# Filter_sim.net
KiCad netlist of a schematic drawn in Altium Designer
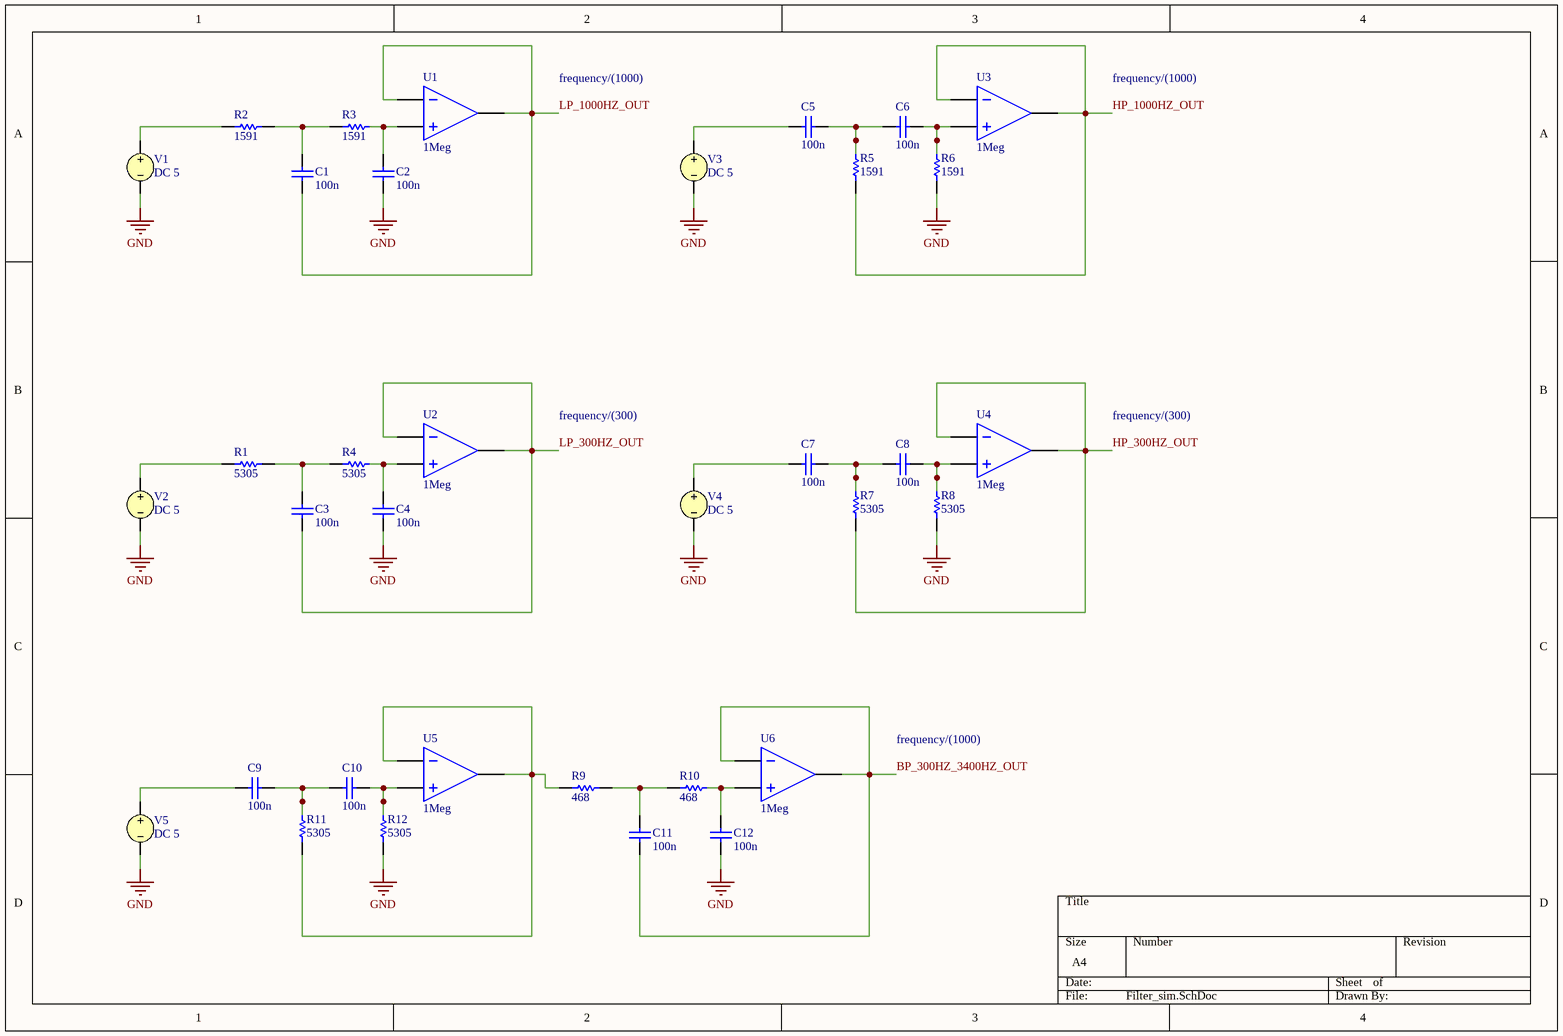
[diagram p0: Filter_sim.SchDoc]

(export (version "E")
  (design (tool "Eeschema 10.0.6"))
  (components
    (comp (ref "C1")
      (value "100n")
      (description "Capacitor")
      (libsource (lib "Simulation Generic Components") (part "Capacitor"))
    )
    (comp (ref "C2")
      (value "100n")
      (description "Capacitor")
      (libsource (lib "Simulation Generic Components") (part "Capacitor"))
    )
    (comp (ref "C3")
      (value "100n")
      (description "Capacitor")
      (libsource (lib "Simulation Generic Components") (part "Capacitor"))
    )
    (comp (ref "C4")
      (value "100n")
      (description "Capacitor")
      (libsource (lib "Simulation Generic Components") (part "Capacitor"))
    )
    (comp (ref "C5")
      (value "100n")
      (description "Capacitor")
      (libsource (lib "Simulation Generic Components") (part "Capacitor"))
    )
    (comp (ref "C6")
      (value "100n")
      (description "Capacitor")
      (libsource (lib "Simulation Generic Components") (part "Capacitor"))
    )
    (comp (ref "C7")
      (value "100n")
      (description "Capacitor")
      (libsource (lib "Simulation Generic Components") (part "Capacitor"))
    )
    (comp (ref "C8")
      (value "100n")
      (description "Capacitor")
      (libsource (lib "Simulation Generic Components") (part "Capacitor"))
    )
    (comp (ref "C9")
      (value "100n")
      (description "Capacitor")
      (libsource (lib "Simulation Generic Components") (part "Capacitor"))
    )
    (comp (ref "C10")
      (value "100n")
      (description "Capacitor")
      (libsource (lib "Simulation Generic Components") (part "Capacitor"))
    )
    (comp (ref "C11")
      (value "100n")
      (description "Capacitor")
      (libsource (lib "Simulation Generic Components") (part "Capacitor"))
    )
    (comp (ref "C12")
      (value "100n")
      (description "Capacitor")
      (libsource (lib "Simulation Generic Components") (part "Capacitor"))
    )
    (comp (ref "R1")
      (value "5305")
      (description "Resistor")
      (libsource (lib "Simulation Generic Components") (part "Resistor"))
    )
    (comp (ref "R2")
      (value "1591")
      (description "Resistor")
      (libsource (lib "Simulation Generic Components") (part "Resistor"))
    )
    (comp (ref "R3")
      (value "1591")
      (description "Resistor")
      (libsource (lib "Simulation Generic Components") (part "Resistor"))
    )
    (comp (ref "R4")
      (value "5305")
      (description "Resistor")
      (libsource (lib "Simulation Generic Components") (part "Resistor"))
    )
    (comp (ref "R5")
      (value "1591")
      (description "Resistor")
      (libsource (lib "Simulation Generic Components") (part "Resistor"))
    )
    (comp (ref "R6")
      (value "1591")
      (description "Resistor")
      (libsource (lib "Simulation Generic Components") (part "Resistor"))
    )
    (comp (ref "R7")
      (value "5305")
      (description "Resistor")
      (libsource (lib "Simulation Generic Components") (part "Resistor"))
    )
    (comp (ref "R8")
      (value "5305")
      (description "Resistor")
      (libsource (lib "Simulation Generic Components") (part "Resistor"))
    )
    (comp (ref "R9")
      (value "468")
      (description "Resistor")
      (libsource (lib "Simulation Generic Components") (part "Resistor"))
    )
    (comp (ref "R10")
      (value "468")
      (description "Resistor")
      (libsource (lib "Simulation Generic Components") (part "Resistor"))
    )
    (comp (ref "R11")
      (value "5305")
      (description "Resistor")
      (libsource (lib "Simulation Generic Components") (part "Resistor"))
    )
    (comp (ref "R12")
      (value "5305")
      (description "Resistor")
      (libsource (lib "Simulation Generic Components") (part "Resistor"))
    )
    (comp (ref "U1")
      (value "Ideal Operational Amplifier")
      (fields (field (name "GAIN") "1Meg"))
      (libsource (lib "Simulation Generic Components") (part "OpAmp"))
    )
    (comp (ref "U2")
      (value "Ideal Operational Amplifier")
      (fields (field (name "GAIN") "1Meg"))
      (libsource (lib "Simulation Generic Components") (part "OpAmp"))
    )
    (comp (ref "U3")
      (value "Ideal Operational Amplifier")
      (fields (field (name "GAIN") "1Meg"))
      (libsource (lib "Simulation Generic Components") (part "OpAmp"))
    )
    (comp (ref "U4")
      (value "Ideal Operational Amplifier")
      (fields (field (name "GAIN") "1Meg"))
      (libsource (lib "Simulation Generic Components") (part "OpAmp"))
    )
    (comp (ref "U5")
      (value "Ideal Operational Amplifier")
      (fields (field (name "GAIN") "1Meg"))
      (libsource (lib "Simulation Generic Components") (part "OpAmp"))
    )
    (comp (ref "U6")
      (value "Ideal Operational Amplifier")
      (fields (field (name "GAIN") "1Meg"))
      (libsource (lib "Simulation Generic Components") (part "OpAmp"))
    )
    (comp (ref "V1")
      (value "DC 5")
      (description "Voltage Source")
      (fields (field (name "PUBLISHER") "Altium Limited"))
      (libsource (lib "Simulation Generic Components") (part "VSRC"))
    )
    (comp (ref "V2")
      (value "DC 5")
      (description "Voltage Source")
      (fields (field (name "PUBLISHER") "Altium Limited"))
      (libsource (lib "Simulation Generic Components") (part "VSRC"))
    )
    (comp (ref "V3")
      (value "DC 5")
      (description "Voltage Source")
      (fields (field (name "PUBLISHER") "Altium Limited"))
      (libsource (lib "Simulation Generic Components") (part "VSRC"))
    )
    (comp (ref "V4")
      (value "DC 5")
      (description "Voltage Source")
      (fields (field (name "PUBLISHER") "Altium Limited"))
      (libsource (lib "Simulation Generic Components") (part "VSRC"))
    )
    (comp (ref "V5")
      (value "DC 5")
      (description "Voltage Source")
      (fields (field (name "PUBLISHER") "Altium Limited"))
      (libsource (lib "Simulation Generic Components") (part "VSRC"))
    )
  )
  (nets
    (net (code "1") (name "/BP_300HZ_3400HZ_OUT") (class "Default")
      (node (ref "C11") (pin "2") (pinfunction "2_2") (pintype "passive"))
      (node (ref "U6") (pin "1") (pinfunction "IN-_1") (pintype "passive"))
      (node (ref "U6") (pin "3") (pinfunction "OUT_3") (pintype "passive"))
    )
    (net (code "2") (name "/HP_300HZ_OUT") (class "Default")
      (node (ref "R7") (pin "2") (pinfunction "2_2") (pintype "passive"))
      (node (ref "U4") (pin "1") (pinfunction "IN-_1") (pintype "passive"))
      (node (ref "U4") (pin "3") (pinfunction "OUT_3") (pintype "passive"))
    )
    (net (code "3") (name "/HP_1000HZ_OUT") (class "Default")
      (node (ref "R5") (pin "2") (pinfunction "2_2") (pintype "passive"))
      (node (ref "U3") (pin "1") (pinfunction "IN-_1") (pintype "passive"))
      (node (ref "U3") (pin "3") (pinfunction "OUT_3") (pintype "passive"))
    )
    (net (code "4") (name "/LP_300HZ_OUT") (class "Default")
      (node (ref "C3") (pin "2") (pinfunction "2_2") (pintype "passive"))
      (node (ref "U2") (pin "1") (pinfunction "IN-_1") (pintype "passive"))
      (node (ref "U2") (pin "3") (pinfunction "OUT_3") (pintype "passive"))
    )
    (net (code "5") (name "/LP_1000HZ_OUT") (class "Default")
      (node (ref "C1") (pin "2") (pinfunction "2_2") (pintype "passive"))
      (node (ref "U1") (pin "1") (pinfunction "IN-_1") (pintype "passive"))
      (node (ref "U1") (pin "3") (pinfunction "OUT_3") (pintype "passive"))
    )
    (net (code "6") (name "GND") (class "Default")
      (node (ref "C12") (pin "1") (pinfunction "1_1") (pintype "passive"))
      (node (ref "C2") (pin "1") (pinfunction "1_1") (pintype "passive"))
      (node (ref "C4") (pin "1") (pinfunction "1_1") (pintype "passive"))
      (node (ref "R12") (pin "2") (pinfunction "2_2") (pintype "passive"))
      (node (ref "R6") (pin "2") (pinfunction "2_2") (pintype "passive"))
      (node (ref "R8") (pin "2") (pinfunction "2_2") (pintype "passive"))
      (node (ref "V1") (pin "2") (pinfunction "2_2") (pintype "passive"))
      (node (ref "V2") (pin "2") (pinfunction "2_2") (pintype "passive"))
      (node (ref "V3") (pin "2") (pinfunction "2_2") (pintype "passive"))
      (node (ref "V4") (pin "2") (pinfunction "2_2") (pintype "passive"))
      (node (ref "V5") (pin "2") (pinfunction "2_2") (pintype "passive"))
    )
    (net (code "7") (name "Net-(C1-Pad1)") (class "Default")
      (node (ref "C1") (pin "1") (pinfunction "1_1") (pintype "passive"))
      (node (ref "R2") (pin "1") (pinfunction "1_1") (pintype "passive"))
      (node (ref "R3") (pin "2") (pinfunction "2_2") (pintype "passive"))
    )
    (net (code "8") (name "Net-(C3-Pad1)") (class "Default")
      (node (ref "C3") (pin "1") (pinfunction "1_1") (pintype "passive"))
      (node (ref "R1") (pin "1") (pinfunction "1_1") (pintype "passive"))
      (node (ref "R4") (pin "2") (pinfunction "2_2") (pintype "passive"))
    )
    (net (code "9") (name "Net-(C5-Pad1)") (class "Default")
      (node (ref "C5") (pin "1") (pinfunction "1_1") (pintype "passive"))
      (node (ref "V3") (pin "1") (pinfunction "1_1") (pintype "passive"))
    )
    (net (code "10") (name "Net-(C5-Pad2)") (class "Default")
      (node (ref "C5") (pin "2") (pinfunction "2_2") (pintype "passive"))
      (node (ref "C6") (pin "2") (pinfunction "2_2") (pintype "passive"))
      (node (ref "R5") (pin "1") (pinfunction "1_1") (pintype "passive"))
    )
    (net (code "11") (name "Net-(C7-Pad1)") (class "Default")
      (node (ref "C7") (pin "1") (pinfunction "1_1") (pintype "passive"))
      (node (ref "V4") (pin "1") (pinfunction "1_1") (pintype "passive"))
    )
    (net (code "12") (name "Net-(C7-Pad2)") (class "Default")
      (node (ref "C7") (pin "2") (pinfunction "2_2") (pintype "passive"))
      (node (ref "C8") (pin "2") (pinfunction "2_2") (pintype "passive"))
      (node (ref "R7") (pin "1") (pinfunction "1_1") (pintype "passive"))
    )
    (net (code "13") (name "Net-(C9-Pad1)") (class "Default")
      (node (ref "C9") (pin "1") (pinfunction "1_1") (pintype "passive"))
      (node (ref "V5") (pin "1") (pinfunction "1_1") (pintype "passive"))
    )
    (net (code "14") (name "Net-(C10-Pad2)") (class "Default")
      (node (ref "C10") (pin "2") (pinfunction "2_2") (pintype "passive"))
      (node (ref "C9") (pin "2") (pinfunction "2_2") (pintype "passive"))
      (node (ref "R11") (pin "1") (pinfunction "1_1") (pintype "passive"))
    )
    (net (code "15") (name "Net-(C11-Pad1)") (class "Default")
      (node (ref "C11") (pin "1") (pinfunction "1_1") (pintype "passive"))
      (node (ref "R10") (pin "2") (pinfunction "2_2") (pintype "passive"))
      (node (ref "R9") (pin "1") (pinfunction "1_1") (pintype "passive"))
    )
    (net (code "16") (name "Net-(R1-Pad2)") (class "Default")
      (node (ref "R1") (pin "2") (pinfunction "2_2") (pintype "passive"))
      (node (ref "V2") (pin "1") (pinfunction "1_1") (pintype "passive"))
    )
    (net (code "17") (name "Net-(R2-Pad2)") (class "Default")
      (node (ref "R2") (pin "2") (pinfunction "2_2") (pintype "passive"))
      (node (ref "V1") (pin "1") (pinfunction "1_1") (pintype "passive"))
    )
    (net (code "18") (name "Net-(U1-IN+)") (class "Default")
      (node (ref "C2") (pin "2") (pinfunction "2_2") (pintype "passive"))
      (node (ref "R3") (pin "1") (pinfunction "1_1") (pintype "passive"))
      (node (ref "U1") (pin "2") (pinfunction "IN+_2") (pintype "passive"))
    )
    (net (code "19") (name "Net-(U2-IN+)") (class "Default")
      (node (ref "C4") (pin "2") (pinfunction "2_2") (pintype "passive"))
      (node (ref "R4") (pin "1") (pinfunction "1_1") (pintype "passive"))
      (node (ref "U2") (pin "2") (pinfunction "IN+_2") (pintype "passive"))
    )
    (net (code "20") (name "Net-(U3-IN+)") (class "Default")
      (node (ref "C6") (pin "1") (pinfunction "1_1") (pintype "passive"))
      (node (ref "R6") (pin "1") (pinfunction "1_1") (pintype "passive"))
      (node (ref "U3") (pin "2") (pinfunction "IN+_2") (pintype "passive"))
    )
    (net (code "21") (name "Net-(U4-IN+)") (class "Default")
      (node (ref "C8") (pin "1") (pinfunction "1_1") (pintype "passive"))
      (node (ref "R8") (pin "1") (pinfunction "1_1") (pintype "passive"))
      (node (ref "U4") (pin "2") (pinfunction "IN+_2") (pintype "passive"))
    )
    (net (code "22") (name "Net-(U5-IN+)") (class "Default")
      (node (ref "C10") (pin "1") (pinfunction "1_1") (pintype "passive"))
      (node (ref "R12") (pin "1") (pinfunction "1_1") (pintype "passive"))
      (node (ref "U5") (pin "2") (pinfunction "IN+_2") (pintype "passive"))
    )
    (net (code "23") (name "Net-(U5-IN-)") (class "Default")
      (node (ref "R11") (pin "2") (pinfunction "2_2") (pintype "passive"))
      (node (ref "R9") (pin "2") (pinfunction "2_2") (pintype "passive"))
      (node (ref "U5") (pin "1") (pinfunction "IN-_1") (pintype "passive"))
      (node (ref "U5") (pin "3") (pinfunction "OUT_3") (pintype "passive"))
    )
    (net (code "24") (name "Net-(U6-IN+)") (class "Default")
      (node (ref "C12") (pin "2") (pinfunction "2_2") (pintype "passive"))
      (node (ref "R10") (pin "1") (pinfunction "1_1") (pintype "passive"))
      (node (ref "U6") (pin "2") (pinfunction "IN+_2") (pintype "passive"))
    )
  )
)
